# ip_phone_a_sdram.net
KiCad netlist of a schematic drawn in Altium Designer
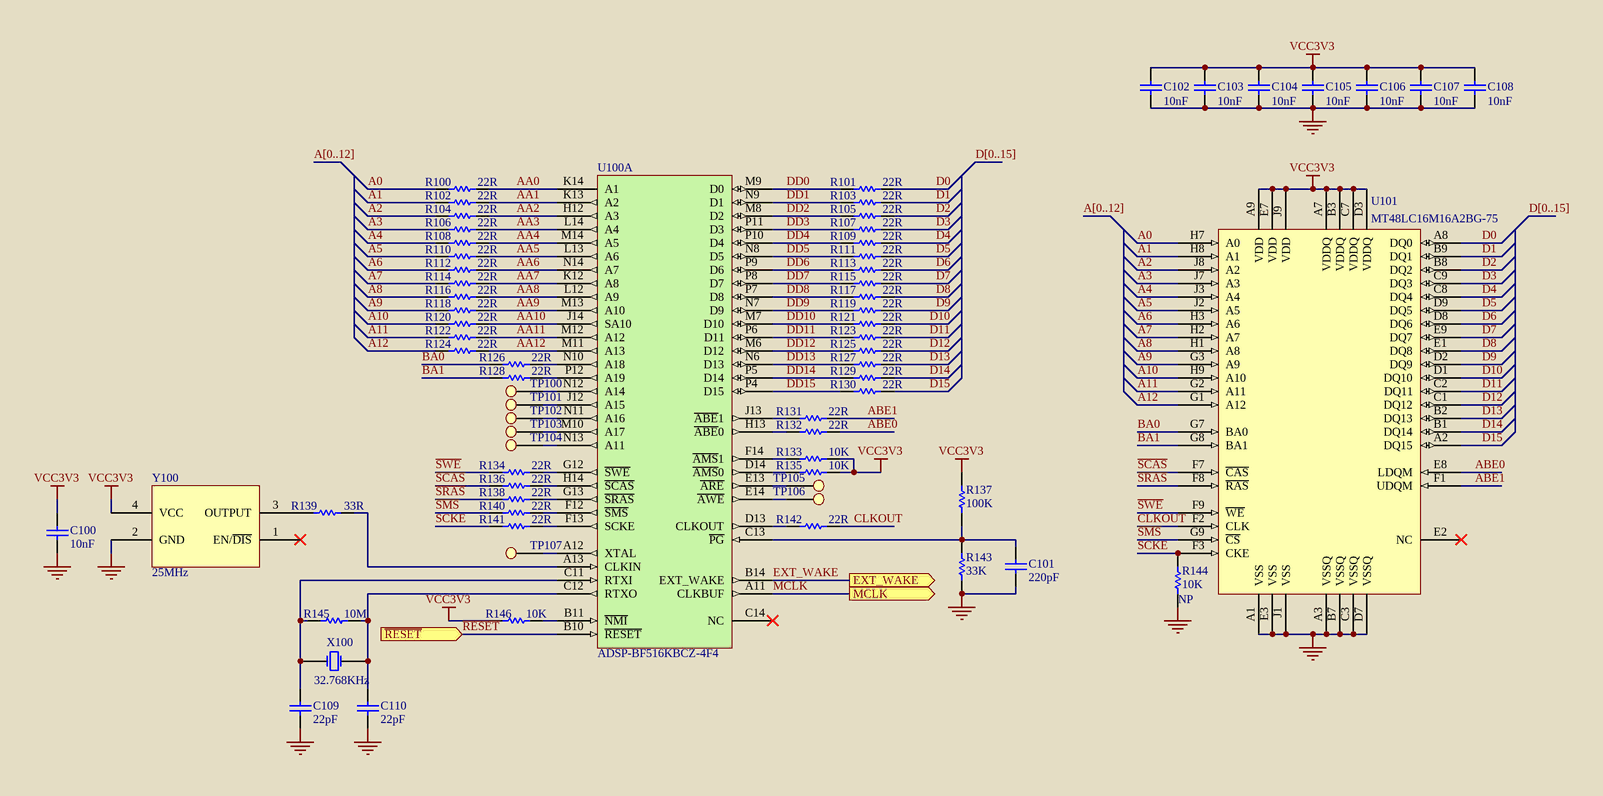
[diagram p0: ip_phone_a_sdram.SchDoc]

(export (version "E")
  (design (tool "Eeschema 10.0.6"))
  (components
    (comp (ref "C100")
      (value "10nF")
      (footprint "ip_phone:CC1005-0402")
      (description "Ceramic Capacitor 10nF 50V X7R 0402")
      (fields (field (name "EVENDORPART#") "810-C1005X7R1C103K") (field (name "MANUFACTURER") "TDK"))
      (libsource (lib "ip_phone") (part "Capacitor"))
    )
    (comp (ref "C101")
      (value "220pF")
      (footprint "ip_phone:CC1005-0402")
      (description "Capacitor")
      (fields (field (name "EVENDORPART#") "311-1035-1-ND") (field (name "MANUFACTURER") "Yageo"))
      (libsource (lib "ip_phone") (part "Capacitor"))
    )
    (comp (ref "C102")
      (value "10nF")
      (footprint "ip_phone:CC1005-0402")
      (description "Ceramic Capacitor 0.01uF 50V X7R 0402")
      (fields (field (name "EVENDORPART#") "810-C1005X7R1C103K") (field (name "MANUFACTURER") "TDK"))
      (libsource (lib "ip_phone") (part "Capacitor"))
    )
    (comp (ref "C103")
      (value "10nF")
      (footprint "ip_phone:CC1005-0402")
      (description "Ceramic Capacitor 0.01uF 50V X7R 0402")
      (fields (field (name "EVENDORPART#") "810-C1005X7R1C103K") (field (name "MANUFACTURER") "TDK"))
      (libsource (lib "ip_phone") (part "Capacitor"))
    )
    (comp (ref "C104")
      (value "10nF")
      (footprint "ip_phone:CC1005-0402")
      (description "Ceramic Capacitor 0.01uF 50V X7R 0402")
      (fields (field (name "EVENDORPART#") "810-C1005X7R1C103K") (field (name "MANUFACTURER") "TDK"))
      (libsource (lib "ip_phone") (part "Capacitor"))
    )
    (comp (ref "C105")
      (value "10nF")
      (footprint "ip_phone:CC1005-0402")
      (description "Ceramic Capacitor 0.01uF 50V X7R 0402")
      (fields (field (name "EVENDORPART#") "810-C1005X7R1C103K") (field (name "MANUFACTURER") "TDK"))
      (libsource (lib "ip_phone") (part "Capacitor"))
    )
    (comp (ref "C106")
      (value "10nF")
      (footprint "ip_phone:CC1005-0402")
      (description "Ceramic Capacitor 0.01uF 50V X7R 0402")
      (fields (field (name "EVENDORPART#") "810-C1005X7R1C103K") (field (name "MANUFACTURER") "TDK"))
      (libsource (lib "ip_phone") (part "Capacitor"))
    )
    (comp (ref "C107")
      (value "10nF")
      (footprint "ip_phone:CC1005-0402")
      (description "Ceramic Capacitor 0.01uF 50V X7R 0402")
      (fields (field (name "EVENDORPART#") "810-C1005X7R1C103K") (field (name "MANUFACTURER") "TDK"))
      (libsource (lib "ip_phone") (part "Capacitor"))
    )
    (comp (ref "C108")
      (value "10nF")
      (footprint "ip_phone:CC1005-0402")
      (description "Ceramic Capacitor 0.01uF 50V X7R 0402")
      (fields (field (name "EVENDORPART#") "810-C1005X7R1C103K") (field (name "MANUFACTURER") "TDK"))
      (libsource (lib "ip_phone") (part "Capacitor"))
    )
    (comp (ref "C109")
      (value "22pF")
      (footprint "ip_phone:CC1005-0402")
      (description "Ceramic Capacitor 22pF 50V 5% C0G 0402")
      (fields
        (field (name "EVENDORPART#") "490-1283-1-ND")
        (field (name "MANUFACTURER") "Murata Electronics North America")
      )
      (libsource (lib "ip_phone") (part "Capacitor"))
    )
    (comp (ref "C110")
      (value "22pF")
      (footprint "ip_phone:CC1005-0402")
      (description "Ceramic Capacitor 22pF 50V 5% C0G 0402")
      (fields
        (field (name "EVENDORPART#") "490-1283-1-ND")
        (field (name "MANUFACTURER") "Murata Electronics North America")
      )
      (libsource (lib "ip_phone") (part "Capacitor"))
    )
    (comp (ref "R100")
      (value "22R")
      (footprint "ip_phone:CR1005-0402")
      (description "Thick Film Resistors SMD 0402 22R 5%  1/16 W")
      (fields (field (name "EVENDORPART#") "71-CRCW0402J-22-E3") (field (name "MANUFACTURER") "Vishay/Dale"))
      (libsource (lib "ip_phone") (part "Resistor"))
    )
    (comp (ref "R101")
      (value "22R")
      (footprint "ip_phone:CR1005-0402")
      (description "Thick Film Resistors SMD 0402 22R 5%  1/16 W")
      (fields (field (name "EVENDORPART#") "71-CRCW0402J-22-E3") (field (name "MANUFACTURER") "Vishay/Dale"))
      (libsource (lib "ip_phone") (part "Resistor"))
    )
    (comp (ref "R102")
      (value "22R")
      (footprint "ip_phone:CR1005-0402")
      (description "Thick Film Resistors SMD 0402 22R 5%  1/16 W")
      (fields (field (name "EVENDORPART#") "71-CRCW0402J-22-E3") (field (name "MANUFACTURER") "Vishay/Dale"))
      (libsource (lib "ip_phone") (part "Resistor"))
    )
    (comp (ref "R103")
      (value "22R")
      (footprint "ip_phone:CR1005-0402")
      (description "Thick Film Resistors SMD 0402 22R 5%  1/16 W")
      (fields (field (name "EVENDORPART#") "71-CRCW0402J-22-E3") (field (name "MANUFACTURER") "Vishay/Dale"))
      (libsource (lib "ip_phone") (part "Resistor"))
    )
    (comp (ref "R104")
      (value "22R")
      (footprint "ip_phone:CR1005-0402")
      (description "Thick Film Resistors SMD 0402 22R 5%  1/16 W")
      (fields (field (name "EVENDORPART#") "71-CRCW0402J-22-E3") (field (name "MANUFACTURER") "Vishay/Dale"))
      (libsource (lib "ip_phone") (part "Resistor"))
    )
    (comp (ref "R105")
      (value "22R")
      (footprint "ip_phone:CR1005-0402")
      (description "Thick Film Resistors SMD 0402 22R 5%  1/16 W")
      (fields (field (name "EVENDORPART#") "71-CRCW0402J-22-E3") (field (name "MANUFACTURER") "Vishay/Dale"))
      (libsource (lib "ip_phone") (part "Resistor"))
    )
    (comp (ref "R106")
      (value "22R")
      (footprint "ip_phone:CR1005-0402")
      (description "Thick Film Resistors SMD 0402 22R 5%  1/16 W")
      (fields (field (name "EVENDORPART#") "71-CRCW0402J-22-E3") (field (name "MANUFACTURER") "Vishay/Dale"))
      (libsource (lib "ip_phone") (part "Resistor"))
    )
    (comp (ref "R107")
      (value "22R")
      (footprint "ip_phone:CR1005-0402")
      (description "Thick Film Resistors SMD 0402 22R 5%  1/16 W")
      (fields (field (name "EVENDORPART#") "71-CRCW0402J-22-E3") (field (name "MANUFACTURER") "Vishay/Dale"))
      (libsource (lib "ip_phone") (part "Resistor"))
    )
    (comp (ref "R108")
      (value "22R")
      (footprint "ip_phone:CR1005-0402")
      (description "Thick Film Resistors SMD 0402 22R 5%  1/16 W")
      (fields (field (name "EVENDORPART#") "71-CRCW0402J-22-E3") (field (name "MANUFACTURER") "Vishay/Dale"))
      (libsource (lib "ip_phone") (part "Resistor"))
    )
    (comp (ref "R109")
      (value "22R")
      (footprint "ip_phone:CR1005-0402")
      (description "Thick Film Resistors SMD 0402 22R 5%  1/16 W")
      (fields (field (name "EVENDORPART#") "71-CRCW0402J-22-E3") (field (name "MANUFACTURER") "Vishay/Dale"))
      (libsource (lib "ip_phone") (part "Resistor"))
    )
    (comp (ref "R110")
      (value "22R")
      (footprint "ip_phone:CR1005-0402")
      (description "Thick Film Resistors SMD 0402 22R 5%  1/16 W")
      (fields (field (name "EVENDORPART#") "71-CRCW0402J-22-E3") (field (name "MANUFACTURER") "Vishay/Dale"))
      (libsource (lib "ip_phone") (part "Resistor"))
    )
    (comp (ref "R111")
      (value "22R")
      (footprint "ip_phone:CR1005-0402")
      (description "Thick Film Resistors SMD 0402 22R 5%  1/16 W")
      (fields (field (name "EVENDORPART#") "71-CRCW0402J-22-E3") (field (name "MANUFACTURER") "Vishay/Dale"))
      (libsource (lib "ip_phone") (part "Resistor"))
    )
    (comp (ref "R112")
      (value "22R")
      (footprint "ip_phone:CR1005-0402")
      (description "Thick Film Resistors SMD 0402 22R 5%  1/16 W")
      (fields (field (name "EVENDORPART#") "71-CRCW0402J-22-E3") (field (name "MANUFACTURER") "Vishay/Dale"))
      (libsource (lib "ip_phone") (part "Resistor"))
    )
    (comp (ref "R113")
      (value "22R")
      (footprint "ip_phone:CR1005-0402")
      (description "Thick Film Resistors SMD 0402 22R 5%  1/16 W")
      (fields (field (name "EVENDORPART#") "71-CRCW0402J-22-E3") (field (name "MANUFACTURER") "Vishay/Dale"))
      (libsource (lib "ip_phone") (part "Resistor"))
    )
    (comp (ref "R114")
      (value "22R")
      (footprint "ip_phone:CR1005-0402")
      (description "Thick Film Resistors SMD 0402 22R 5%  1/16 W")
      (fields (field (name "EVENDORPART#") "71-CRCW0402J-22-E3") (field (name "MANUFACTURER") "Vishay/Dale"))
      (libsource (lib "ip_phone") (part "Resistor"))
    )
    (comp (ref "R115")
      (value "22R")
      (footprint "ip_phone:CR1005-0402")
      (description "Thick Film Resistors SMD 0402 22R 5%  1/16 W")
      (fields (field (name "EVENDORPART#") "71-CRCW0402J-22-E3") (field (name "MANUFACTURER") "Vishay/Dale"))
      (libsource (lib "ip_phone") (part "Resistor"))
    )
    (comp (ref "R116")
      (value "22R")
      (footprint "ip_phone:CR1005-0402")
      (description "Thick Film Resistors SMD 0402 22R 5%  1/16 W")
      (fields (field (name "EVENDORPART#") "71-CRCW0402J-22-E3") (field (name "MANUFACTURER") "Vishay/Dale"))
      (libsource (lib "ip_phone") (part "Resistor"))
    )
    (comp (ref "R117")
      (value "22R")
      (footprint "ip_phone:CR1005-0402")
      (description "Thick Film Resistors SMD 0402 22R 5%  1/16 W")
      (fields (field (name "EVENDORPART#") "71-CRCW0402J-22-E3") (field (name "MANUFACTURER") "Vishay/Dale"))
      (libsource (lib "ip_phone") (part "Resistor"))
    )
    (comp (ref "R118")
      (value "22R")
      (footprint "ip_phone:CR1005-0402")
      (description "Thick Film Resistors SMD 0402 22R 5%  1/16 W")
      (fields (field (name "EVENDORPART#") "71-CRCW0402J-22-E3") (field (name "MANUFACTURER") "Vishay/Dale"))
      (libsource (lib "ip_phone") (part "Resistor"))
    )
    (comp (ref "R119")
      (value "22R")
      (footprint "ip_phone:CR1005-0402")
      (description "Thick Film Resistors SMD 0402 22R 5%  1/16 W")
      (fields (field (name "EVENDORPART#") "71-CRCW0402J-22-E3") (field (name "MANUFACTURER") "Vishay/Dale"))
      (libsource (lib "ip_phone") (part "Resistor"))
    )
    (comp (ref "R120")
      (value "22R")
      (footprint "ip_phone:CR1005-0402")
      (description "Thick Film Resistors SMD 0402 22R 5%  1/16 W")
      (fields (field (name "EVENDORPART#") "71-CRCW0402J-22-E3") (field (name "MANUFACTURER") "Vishay/Dale"))
      (libsource (lib "ip_phone") (part "Resistor"))
    )
    (comp (ref "R121")
      (value "22R")
      (footprint "ip_phone:CR1005-0402")
      (description "Thick Film Resistors SMD 0402 22R 5%  1/16 W")
      (fields (field (name "EVENDORPART#") "71-CRCW0402J-22-E3") (field (name "MANUFACTURER") "Vishay/Dale"))
      (libsource (lib "ip_phone") (part "Resistor"))
    )
    (comp (ref "R122")
      (value "22R")
      (footprint "ip_phone:CR1005-0402")
      (description "Thick Film Resistors SMD 0402 22R 5%  1/16 W")
      (fields (field (name "EVENDORPART#") "71-CRCW0402J-22-E3") (field (name "MANUFACTURER") "Vishay/Dale"))
      (libsource (lib "ip_phone") (part "Resistor"))
    )
    (comp (ref "R123")
      (value "22R")
      (footprint "ip_phone:CR1005-0402")
      (description "Thick Film Resistors SMD 0402 22R 5%  1/16 W")
      (fields (field (name "EVENDORPART#") "71-CRCW0402J-22-E3") (field (name "MANUFACTURER") "Vishay/Dale"))
      (libsource (lib "ip_phone") (part "Resistor"))
    )
    (comp (ref "R124")
      (value "22R")
      (footprint "ip_phone:CR1005-0402")
      (description "Thick Film Resistors SMD 0402 22R 5%  1/16 W")
      (fields (field (name "EVENDORPART#") "71-CRCW0402J-22-E3") (field (name "MANUFACTURER") "Vishay/Dale"))
      (libsource (lib "ip_phone") (part "Resistor"))
    )
    (comp (ref "R125")
      (value "22R")
      (footprint "ip_phone:CR1005-0402")
      (description "Thick Film Resistors SMD 0402 22R 5%  1/16 W")
      (fields (field (name "EVENDORPART#") "71-CRCW0402J-22-E3") (field (name "MANUFACTURER") "Vishay/Dale"))
      (libsource (lib "ip_phone") (part "Resistor"))
    )
    (comp (ref "R126")
      (value "22R")
      (footprint "ip_phone:CR1005-0402")
      (description "Thick Film Resistors SMD 0402 22R 5%  1/16 W")
      (fields (field (name "EVENDORPART#") "71-CRCW0402J-22-E3") (field (name "MANUFACTURER") "Vishay/Dale"))
      (libsource (lib "ip_phone") (part "Resistor"))
    )
    (comp (ref "R127")
      (value "22R")
      (footprint "ip_phone:CR1005-0402")
      (description "Thick Film Resistors SMD 0402 22R 5%  1/16 W")
      (fields (field (name "EVENDORPART#") "71-CRCW0402J-22-E3") (field (name "MANUFACTURER") "Vishay/Dale"))
      (libsource (lib "ip_phone") (part "Resistor"))
    )
    (comp (ref "R128")
      (value "22R")
      (footprint "ip_phone:CR1005-0402")
      (description "Thick Film Resistors SMD 0402 22R 5%  1/16 W")
      (fields (field (name "EVENDORPART#") "71-CRCW0402J-22-E3") (field (name "MANUFACTURER") "Vishay/Dale"))
      (libsource (lib "ip_phone") (part "Resistor"))
    )
    (comp (ref "R129")
      (value "22R")
      (footprint "ip_phone:CR1005-0402")
      (description "Thick Film Resistors SMD 0402 22R 5%  1/16 W")
      (fields (field (name "EVENDORPART#") "71-CRCW0402J-22-E3") (field (name "MANUFACTURER") "Vishay/Dale"))
      (libsource (lib "ip_phone") (part "Resistor"))
    )
    (comp (ref "R130")
      (value "22R")
      (footprint "ip_phone:CR1005-0402")
      (description "Thick Film Resistors SMD 0402 22R 5%  1/16 W")
      (fields (field (name "EVENDORPART#") "71-CRCW0402J-22-E3") (field (name "MANUFACTURER") "Vishay/Dale"))
      (libsource (lib "ip_phone") (part "Resistor"))
    )
    (comp (ref "R131")
      (value "22R")
      (footprint "ip_phone:CR1005-0402")
      (description "Thick Film Resistors SMD 0402 22R 5%  1/16 W")
      (fields (field (name "EVENDORPART#") "71-CRCW0402J-22-E3") (field (name "MANUFACTURER") "Vishay/Dale"))
      (libsource (lib "ip_phone") (part "Resistor"))
    )
    (comp (ref "R132")
      (value "22R")
      (footprint "ip_phone:CR1005-0402")
      (description "Thick Film Resistors SMD 0402 22R 5%  1/16 W")
      (fields (field (name "EVENDORPART#") "71-CRCW0402J-22-E3") (field (name "MANUFACTURER") "Vishay/Dale"))
      (libsource (lib "ip_phone") (part "Resistor"))
    )
    (comp (ref "R133")
      (value "10K")
      (footprint "ip_phone:CR1005-0402")
      (description "Thick Film Resistors SMD 0402 10k 5%  1/16 W")
      (fields (field (name "EVENDORPART#") "311-10KJRCT-ND") (field (name "MANUFACTURER") "Yageo"))
      (libsource (lib "ip_phone") (part "Resistor"))
    )
    (comp (ref "R134")
      (value "22R")
      (footprint "ip_phone:CR1005-0402")
      (description "Thick Film Resistors SMD 0402 22R 5%  1/16 W")
      (fields (field (name "EVENDORPART#") "71-CRCW0402J-22-E3") (field (name "MANUFACTURER") "Vishay/Dale"))
      (libsource (lib "ip_phone") (part "Resistor"))
    )
    (comp (ref "R135")
      (value "10K")
      (footprint "ip_phone:CR1005-0402")
      (description "Thick Film Resistors SMD 0402 10k 5%  1/16 W")
      (fields (field (name "EVENDORPART#") "311-10KJRCT-ND") (field (name "MANUFACTURER") "Yageo"))
      (libsource (lib "ip_phone") (part "Resistor"))
    )
    (comp (ref "R136")
      (value "22R")
      (footprint "ip_phone:CR1005-0402")
      (description "Thick Film Resistors SMD 0402 22R 5%  1/16 W")
      (fields (field (name "EVENDORPART#") "71-CRCW0402J-22-E3") (field (name "MANUFACTURER") "Vishay/Dale"))
      (libsource (lib "ip_phone") (part "Resistor"))
    )
    (comp (ref "R137")
      (value "100K")
      (footprint "ip_phone:CR1005-0402")
      (description "Thick Film Resistors SMD 0402 100K 5%  1/16 W")
      (fields (field (name "EVENDORPART#") "311-100KJRCT-ND") (field (name "MANUFACTURER") "Yageo"))
      (libsource (lib "ip_phone") (part "Resistor"))
    )
    (comp (ref "R138")
      (value "22R")
      (footprint "ip_phone:CR1005-0402")
      (description "Thick Film Resistors SMD 0402 22R 5%  1/16 W")
      (fields (field (name "EVENDORPART#") "71-CRCW0402J-22-E3") (field (name "MANUFACTURER") "Vishay/Dale"))
      (libsource (lib "ip_phone") (part "Resistor"))
    )
    (comp (ref "R139")
      (value "33R")
      (footprint "ip_phone:CR1005-0402")
      (description "Thick Film Resistors SMD 0402 33R 5%  1/16 W")
      (fields (field (name "EVENDORPART#") "311-33JRCT-ND") (field (name "MANUFACTURER") "Yageo"))
      (libsource (lib "ip_phone") (part "Resistor"))
    )
    (comp (ref "R140")
      (value "22R")
      (footprint "ip_phone:CR1005-0402")
      (description "Thick Film Resistors SMD 0402 22R 5%  1/16 W")
      (fields (field (name "EVENDORPART#") "71-CRCW0402J-22-E3") (field (name "MANUFACTURER") "Vishay/Dale"))
      (libsource (lib "ip_phone") (part "Resistor"))
    )
    (comp (ref "R141")
      (value "22R")
      (footprint "ip_phone:CR1005-0402")
      (description "Thick Film Resistors SMD 0402 22R 5%  1/16 W")
      (fields (field (name "EVENDORPART#") "71-CRCW0402J-22-E3") (field (name "MANUFACTURER") "Vishay/Dale"))
      (libsource (lib "ip_phone") (part "Resistor"))
    )
    (comp (ref "R142")
      (value "22R")
      (footprint "ip_phone:CR1005-0402")
      (description "Thick Film Resistors SMD 0402 22R 5%  1/16 W")
      (fields (field (name "EVENDORPART#") "71-CRCW0402J-22-E3") (field (name "MANUFACTURER") "Vishay/Dale"))
      (libsource (lib "ip_phone") (part "Resistor"))
    )
    (comp (ref "R143")
      (value "33K")
      (footprint "ip_phone:CR1005-0402")
      (description "Thick Film Resistors SMD 0402 33K 5%  1/16 W")
      (fields (field (name "EVENDORPART#") "311-33KJRCT-ND") (field (name "MANUFACTURER") "Yageo"))
      (libsource (lib "ip_phone") (part "Resistor"))
    )
    (comp (ref "R144")
      (value "10K")
      (footprint "ip_phone:CR1005-0402_NP")
      (description "Thick Film Resistors SMD 0402 10K 5%  1/16 W")
      (fields
        (field (name "EVENDORPART#") "311-10KJRCT-ND")
        (field (name "MANUFACTURER") "Yageo")
        (field (name "NP") "NP")
      )
      (libsource (lib "ip_phone") (part "Resistor"))
    )
    (comp (ref "R145")
      (value "10M")
      (footprint "ip_phone:CR1005-0402")
      (description "Thick Film Resistors SMD 0402 10M 5%  1/16 W")
      (fields
        (field (name "EVENDORPART#") "RMCF0402JT10M0CT-ND")
        (field (name "MANUFACTURER") "Stackpole Electronics Inc")
      )
      (libsource (lib "ip_phone") (part "Resistor"))
    )
    (comp (ref "R146")
      (value "10K")
      (footprint "ip_phone:CR1005-0402")
      (description "Thick Film Resistors SMD 0402 10K 5%  1/16 W")
      (fields (field (name "EVENDORPART#") "311-10KJRCT-ND") (field (name "MANUFACTURER") "Yageo"))
      (libsource (lib "ip_phone") (part "Resistor"))
    )
    (comp (ref "TP100")
      (value "Test Point")
      (footprint "ip_phone:Test Point")
      (fields (field (name "EVENDORPART#") "NÃO SE APLICA"))
      (libsource (lib "ip_phone") (part "Test Point"))
    )
    (comp (ref "TP101")
      (value "Test Point")
      (footprint "ip_phone:Test Point")
      (fields (field (name "EVENDORPART#") "NÃO SE APLICA"))
      (libsource (lib "ip_phone") (part "Test Point"))
    )
    (comp (ref "TP102")
      (value "Test Point")
      (footprint "ip_phone:Test Point")
      (fields (field (name "EVENDORPART#") "NÃO SE APLICA"))
      (libsource (lib "ip_phone") (part "Test Point"))
    )
    (comp (ref "TP103")
      (value "Test Point")
      (footprint "ip_phone:Test Point")
      (fields (field (name "EVENDORPART#") "NÃO SE APLICA"))
      (libsource (lib "ip_phone") (part "Test Point"))
    )
    (comp (ref "TP104")
      (value "Test Point")
      (footprint "ip_phone:Test Point")
      (fields (field (name "EVENDORPART#") "NÃO SE APLICA"))
      (libsource (lib "ip_phone") (part "Test Point"))
    )
    (comp (ref "TP105")
      (value "Test Point")
      (footprint "ip_phone:Test Point")
      (fields (field (name "EVENDORPART#") "NÃO SE APLICA"))
      (libsource (lib "ip_phone") (part "Test Point"))
    )
    (comp (ref "TP106")
      (value "Test Point")
      (footprint "ip_phone:Test Point")
      (fields (field (name "EVENDORPART#") "NÃO SE APLICA"))
      (libsource (lib "ip_phone") (part "Test Point"))
    )
    (comp (ref "TP107")
      (value "Test Point")
      (footprint "ip_phone:Test Point")
      (fields (field (name "EVENDORPART#") "NÃO SE APLICA"))
      (libsource (lib "ip_phone") (part "Test Point"))
    )
    (comp (ref "U100")
      (value "ADSP-BF516KBCZ-4F4")
      (footprint "ip_phone:BGA168")
      (description "Low Power Blackfin with Advanced Embedded Connectivity")
      (fields (field (name "MANUFACTURER") "Analog Device"))
      (libsource (lib "ip_phone") (part "ADSP-BF516KBCZ-4F4"))
    )
    (comp (ref "U101")
      (value "MT48LC16M16A2BG-75")
      (footprint "ip_phone:VFBGA54")
      (description "SDRAM 256M-Bit 16Mx16 3.3V 54-Pin VFBGA Tray")
      (fields (field (name "EVENDORPART#") "MT48LC16M16A2BG-75 IT:D") (field (name "MANUFACTURER") "Micron"))
      (libsource (lib "ip_phone") (part "MT48LC16M16A2BG-75"))
    )
    (comp (ref "X100")
      (value "32.768KHz")
      (footprint "ip_phone:XTAL_32.768kHz")
      (description "Crystal 32.768KHz")
      (fields
        (field (name "EVENDORPART#") "732-MC30632.7680KA0R")
        (field (name "PART#") "MC-306 32.7680K-A0:ROHS")
      )
      (libsource (lib "ip_phone") (part "XTAL_32.768KHz"))
    )
    (comp (ref "Y100")
      (value "25MHz")
      (footprint "ip_phone:OSC_25MHz")
      (description "Crystal Clock Oscillator 25MHz  50ppm 3.3V")
      (fields (field (name "EVENDORPART#") "300-8254-1-ND") (field (name "PART#") "ASFL1-25.000MHZ-EC-T"))
      (libsource (lib "ip_phone") (part "Oscillator_25MHz"))
    )
  )
  (nets
    (net (code "1") (name "/A0") (class "Default")
      (node (ref "R100") (pin "1") (pinfunction "1_1") (pintype "passive"))
      (node (ref "U101") (pin "H7") (pinfunction "A0_H7") (pintype "input"))
    )
    (net (code "2") (name "/A1") (class "Default")
      (node (ref "R102") (pin "1") (pinfunction "1_1") (pintype "passive"))
      (node (ref "U101") (pin "H8") (pinfunction "A1_H8") (pintype "input"))
    )
    (net (code "3") (name "/A2") (class "Default")
      (node (ref "R104") (pin "1") (pinfunction "1_1") (pintype "passive"))
      (node (ref "U101") (pin "J8") (pinfunction "A2_J8") (pintype "input"))
    )
    (net (code "4") (name "/A3") (class "Default")
      (node (ref "R106") (pin "1") (pinfunction "1_1") (pintype "passive"))
      (node (ref "U101") (pin "J7") (pinfunction "A3_J7") (pintype "input"))
    )
    (net (code "5") (name "/A4") (class "Default")
      (node (ref "R108") (pin "1") (pinfunction "1_1") (pintype "passive"))
      (node (ref "U101") (pin "J3") (pinfunction "A4_J3") (pintype "input"))
    )
    (net (code "6") (name "/A5") (class "Default")
      (node (ref "R110") (pin "1") (pinfunction "1_1") (pintype "passive"))
      (node (ref "U101") (pin "J2") (pinfunction "A5_J2") (pintype "input"))
    )
    (net (code "7") (name "/A6") (class "Default")
      (node (ref "R112") (pin "1") (pinfunction "1_1") (pintype "passive"))
      (node (ref "U101") (pin "H3") (pinfunction "A6_H3") (pintype "input"))
    )
    (net (code "8") (name "/A7") (class "Default")
      (node (ref "R114") (pin "1") (pinfunction "1_1") (pintype "passive"))
      (node (ref "U101") (pin "H2") (pinfunction "A7_H2") (pintype "input"))
    )
    (net (code "9") (name "/A8") (class "Default")
      (node (ref "R116") (pin "1") (pinfunction "1_1") (pintype "passive"))
      (node (ref "U101") (pin "H1") (pinfunction "A8_H1") (pintype "input"))
    )
    (net (code "10") (name "/A9") (class "Default")
      (node (ref "R118") (pin "1") (pinfunction "1_1") (pintype "passive"))
      (node (ref "U101") (pin "G3") (pinfunction "A9_G3") (pintype "input"))
    )
    (net (code "11") (name "/A10") (class "Default")
      (node (ref "R120") (pin "1") (pinfunction "1_1") (pintype "passive"))
      (node (ref "U101") (pin "H9") (pinfunction "A10_H9") (pintype "input"))
    )
    (net (code "12") (name "/A11") (class "Default")
      (node (ref "R122") (pin "1") (pinfunction "1_1") (pintype "passive"))
      (node (ref "U101") (pin "G2") (pinfunction "A11_G2") (pintype "input"))
    )
    (net (code "13") (name "/A12") (class "Default")
      (node (ref "R124") (pin "1") (pinfunction "1_1") (pintype "passive"))
      (node (ref "U101") (pin "G1") (pinfunction "A12_G1") (pintype "input"))
    )
    (net (code "14") (name "/AA0") (class "Default")
      (node (ref "R100") (pin "2") (pinfunction "2_2") (pintype "passive"))
      (node (ref "U100") (pin "K14") (pinfunction "A1_K14") (pintype "passive"))
    )
    (net (code "15") (name "/AA1") (class "Default")
      (node (ref "R102") (pin "2") (pinfunction "2_2") (pintype "passive"))
      (node (ref "U100") (pin "K13") (pinfunction "A2_K13") (pintype "output"))
    )
    (net (code "16") (name "/AA2") (class "Default")
      (node (ref "R104") (pin "2") (pinfunction "2_2") (pintype "passive"))
      (node (ref "U100") (pin "H12") (pinfunction "A3_H12") (pintype "output"))
    )
    (net (code "17") (name "/AA3") (class "Default")
      (node (ref "R106") (pin "2") (pinfunction "2_2") (pintype "passive"))
      (node (ref "U100") (pin "L14") (pinfunction "A4_L14") (pintype "output"))
    )
    (net (code "18") (name "/AA4") (class "Default")
      (node (ref "R108") (pin "2") (pinfunction "2_2") (pintype "passive"))
      (node (ref "U100") (pin "M14") (pinfunction "A5_M14") (pintype "output"))
    )
    (net (code "19") (name "/AA5") (class "Default")
      (node (ref "R110") (pin "2") (pinfunction "2_2") (pintype "passive"))
      (node (ref "U100") (pin "L13") (pinfunction "A6_L13") (pintype "output"))
    )
    (net (code "20") (name "/AA6") (class "Default")
      (node (ref "R112") (pin "2") (pinfunction "2_2") (pintype "passive"))
      (node (ref "U100") (pin "N14") (pinfunction "A7_N14") (pintype "output"))
    )
    (net (code "21") (name "/AA7") (class "Default")
      (node (ref "R114") (pin "2") (pinfunction "2_2") (pintype "passive"))
      (node (ref "U100") (pin "K12") (pinfunction "A8_K12") (pintype "output"))
    )
    (net (code "22") (name "/AA8") (class "Default")
      (node (ref "R116") (pin "2") (pinfunction "2_2") (pintype "passive"))
      (node (ref "U100") (pin "L12") (pinfunction "A9_L12") (pintype "output"))
    )
    (net (code "23") (name "/AA9") (class "Default")
      (node (ref "R118") (pin "2") (pinfunction "2_2") (pintype "passive"))
      (node (ref "U100") (pin "M13") (pinfunction "A10_M13") (pintype "output"))
    )
    (net (code "24") (name "/AA10") (class "Default")
      (node (ref "R120") (pin "2") (pinfunction "2_2") (pintype "passive"))
      (node (ref "U100") (pin "J14") (pinfunction "SA10_J14") (pintype "output"))
    )
    (net (code "25") (name "/AA11") (class "Default")
      (node (ref "R122") (pin "2") (pinfunction "2_2") (pintype "passive"))
      (node (ref "U100") (pin "M12") (pinfunction "A12_M12") (pintype "output"))
    )
    (net (code "26") (name "/AA12") (class "Default")
      (node (ref "R124") (pin "2") (pinfunction "2_2") (pintype "passive"))
      (node (ref "U100") (pin "M11") (pinfunction "A13_M11") (pintype "output"))
    )
    (net (code "27") (name "/ABE0") (class "Default")
      (node (ref "R132") (pin "2") (pinfunction "2_2") (pintype "passive"))
      (node (ref "U101") (pin "E8") (pinfunction "LDQM_E8") (pintype "input"))
    )
    (net (code "28") (name "/ABE1") (class "Default")
      (node (ref "R131") (pin "2") (pinfunction "2_2") (pintype "passive"))
      (node (ref "U101") (pin "F1") (pinfunction "UDQM_F1") (pintype "input"))
    )
    (net (code "30") (name "/BA0") (class "Default")
      (node (ref "R126") (pin "1") (pinfunction "1_1") (pintype "passive"))
      (node (ref "U101") (pin "G7") (pinfunction "BA0_G7") (pintype "input"))
    )
    (net (code "31") (name "/BA1") (class "Default")
      (node (ref "R128") (pin "1") (pinfunction "1_1") (pintype "passive"))
      (node (ref "U101") (pin "G8") (pinfunction "BA1_G8") (pintype "input"))
    )
    (net (code "32") (name "/CLKOUT") (class "Default")
      (node (ref "R142") (pin "2") (pinfunction "2_2") (pintype "passive"))
      (node (ref "U101") (pin "F2") (pinfunction "CLK_F2") (pintype "input"))
    )
    (net (code "33") (name "/D0") (class "Default")
      (node (ref "R101") (pin "2") (pinfunction "2_2") (pintype "passive"))
      (node (ref "U101") (pin "A8") (pinfunction "DQ0_A8") (pintype "bidirectional"))
    )
    (net (code "34") (name "/D1") (class "Default")
      (node (ref "R103") (pin "2") (pinfunction "2_2") (pintype "passive"))
      (node (ref "U101") (pin "B9") (pinfunction "DQ1_B9") (pintype "bidirectional"))
    )
    (net (code "35") (name "/D2") (class "Default")
      (node (ref "R105") (pin "2") (pinfunction "2_2") (pintype "passive"))
      (node (ref "U101") (pin "B8") (pinfunction "DQ2_B8") (pintype "bidirectional"))
    )
    (net (code "36") (name "/D3") (class "Default")
      (node (ref "R107") (pin "2") (pinfunction "2_2") (pintype "passive"))
      (node (ref "U101") (pin "C9") (pinfunction "DQ3_C9") (pintype "bidirectional"))
    )
    (net (code "37") (name "/D4") (class "Default")
      (node (ref "R109") (pin "2") (pinfunction "2_2") (pintype "passive"))
      (node (ref "U101") (pin "C8") (pinfunction "DQ4_C8") (pintype "bidirectional"))
    )
    (net (code "38") (name "/D5") (class "Default")
      (node (ref "R111") (pin "2") (pinfunction "2_2") (pintype "passive"))
      (node (ref "U101") (pin "D9") (pinfunction "DQ5_D9") (pintype "bidirectional"))
    )
    (net (code "39") (name "/D6") (class "Default")
      (node (ref "R113") (pin "2") (pinfunction "2_2") (pintype "passive"))
      (node (ref "U101") (pin "D8") (pinfunction "DQ6_D8") (pintype "bidirectional"))
    )
    (net (code "40") (name "/D7") (class "Default")
      (node (ref "R115") (pin "2") (pinfunction "2_2") (pintype "passive"))
      (node (ref "U101") (pin "E9") (pinfunction "DQ7_E9") (pintype "bidirectional"))
    )
    (net (code "41") (name "/D8") (class "Default")
      (node (ref "R117") (pin "2") (pinfunction "2_2") (pintype "passive"))
      (node (ref "U101") (pin "E1") (pinfunction "DQ8_E1") (pintype "bidirectional"))
    )
    (net (code "42") (name "/D9") (class "Default")
      (node (ref "R119") (pin "2") (pinfunction "2_2") (pintype "passive"))
      (node (ref "U101") (pin "D2") (pinfunction "DQ9_D2") (pintype "bidirectional"))
    )
    (net (code "43") (name "/D10") (class "Default")
      (node (ref "R121") (pin "2") (pinfunction "2_2") (pintype "passive"))
      (node (ref "U101") (pin "D1") (pinfunction "DQ10_D1") (pintype "bidirectional"))
    )
    (net (code "44") (name "/D11") (class "Default")
      (node (ref "R123") (pin "2") (pinfunction "2_2") (pintype "passive"))
      (node (ref "U101") (pin "C2") (pinfunction "DQ11_C2") (pintype "bidirectional"))
    )
    (net (code "45") (name "/D12") (class "Default")
      (node (ref "R125") (pin "2") (pinfunction "2_2") (pintype "passive"))
      (node (ref "U101") (pin "C1") (pinfunction "DQ12_C1") (pintype "bidirectional"))
    )
    (net (code "46") (name "/D13") (class "Default")
      (node (ref "R127") (pin "2") (pinfunction "2_2") (pintype "passive"))
      (node (ref "U101") (pin "B2") (pinfunction "DQ13_B2") (pintype "bidirectional"))
    )
    (net (code "47") (name "/D14") (class "Default")
      (node (ref "R129") (pin "2") (pinfunction "2_2") (pintype "passive"))
      (node (ref "U101") (pin "B1") (pinfunction "DQ14_B1") (pintype "bidirectional"))
    )
    (net (code "48") (name "/D15") (class "Default")
      (node (ref "R130") (pin "2") (pinfunction "2_2") (pintype "passive"))
      (node (ref "U101") (pin "A2") (pinfunction "DQ15_A2") (pintype "bidirectional"))
    )
    (net (code "49") (name "/DD0") (class "Default")
      (node (ref "R101") (pin "1") (pinfunction "1_1") (pintype "passive"))
      (node (ref "U100") (pin "M9") (pinfunction "D0_M9") (pintype "bidirectional"))
    )
    (net (code "50") (name "/DD1") (class "Default")
      (node (ref "R103") (pin "1") (pinfunction "1_1") (pintype "passive"))
      (node (ref "U100") (pin "N9") (pinfunction "D1_N9") (pintype "bidirectional"))
    )
    (net (code "51") (name "/DD2") (class "Default")
      (node (ref "R105") (pin "1") (pinfunction "1_1") (pintype "passive"))
      (node (ref "U100") (pin "M8") (pinfunction "D2_M8") (pintype "bidirectional"))
    )
    (net (code "52") (name "/DD3") (class "Default")
      (node (ref "R107") (pin "1") (pinfunction "1_1") (pintype "passive"))
      (node (ref "U100") (pin "P11") (pinfunction "D3_P11") (pintype "bidirectional"))
    )
    (net (code "53") (name "/DD4") (class "Default")
      (node (ref "R109") (pin "1") (pinfunction "1_1") (pintype "passive"))
      (node (ref "U100") (pin "P10") (pinfunction "D4_P10") (pintype "bidirectional"))
    )
    (net (code "54") (name "/DD5") (class "Default")
      (node (ref "R111") (pin "1") (pinfunction "1_1") (pintype "passive"))
      (node (ref "U100") (pin "N8") (pinfunction "D5_N8") (pintype "bidirectional"))
    )
    (net (code "55") (name "/DD6") (class "Default")
      (node (ref "R113") (pin "1") (pinfunction "1_1") (pintype "passive"))
      (node (ref "U100") (pin "P9") (pinfunction "D6_P9") (pintype "bidirectional"))
    )
    (net (code "56") (name "/DD7") (class "Default")
      (node (ref "R115") (pin "1") (pinfunction "1_1") (pintype "passive"))
      (node (ref "U100") (pin "P8") (pinfunction "D7_P8") (pintype "bidirectional"))
    )
    (net (code "57") (name "/DD8") (class "Default")
      (node (ref "R117") (pin "1") (pinfunction "1_1") (pintype "passive"))
      (node (ref "U100") (pin "P7") (pinfunction "D8_P7") (pintype "bidirectional"))
    )
    (net (code "58") (name "/DD9") (class "Default")
      (node (ref "R119") (pin "1") (pinfunction "1_1") (pintype "passive"))
      (node (ref "U100") (pin "N7") (pinfunction "D9_N7") (pintype "bidirectional"))
    )
    (net (code "59") (name "/DD10") (class "Default")
      (node (ref "R121") (pin "1") (pinfunction "1_1") (pintype "passive"))
      (node (ref "U100") (pin "M7") (pinfunction "D10_M7") (pintype "bidirectional"))
    )
    (net (code "60") (name "/DD11") (class "Default")
      (node (ref "R123") (pin "1") (pinfunction "1_1") (pintype "passive"))
      (node (ref "U100") (pin "P6") (pinfunction "D11_P6") (pintype "bidirectional"))
    )
    (net (code "61") (name "/DD12") (class "Default")
      (node (ref "R125") (pin "1") (pinfunction "1_1") (pintype "passive"))
      (node (ref "U100") (pin "M6") (pinfunction "D12_M6") (pintype "bidirectional"))
    )
    (net (code "62") (name "/DD13") (class "Default")
      (node (ref "R127") (pin "1") (pinfunction "1_1") (pintype "passive"))
      (node (ref "U100") (pin "N6") (pinfunction "D13_N6") (pintype "bidirectional"))
    )
    (net (code "63") (name "/DD14") (class "Default")
      (node (ref "R129") (pin "1") (pinfunction "1_1") (pintype "passive"))
      (node (ref "U100") (pin "P5") (pinfunction "D14_P5") (pintype "bidirectional"))
    )
    (net (code "64") (name "/DD15") (class "Default")
      (node (ref "R130") (pin "1") (pinfunction "1_1") (pintype "passive"))
      (node (ref "U100") (pin "P4") (pinfunction "D15_P4") (pintype "bidirectional"))
    )
    (net (code "66") (name "/EXT_WAKE") (class "Default")
      (node (ref "U100") (pin "B14") (pinfunction "EXT_WAKE_B14") (pintype "output"))
    )
    (net (code "67") (name "/MCLK") (class "Default")
      (node (ref "U100") (pin "A11") (pinfunction "CLKBUF_A11") (pintype "output"))
    )
    (net (code "68") (name "/SCKE") (class "Default")
      (node (ref "R141") (pin "1") (pinfunction "1_1") (pintype "passive"))
      (node (ref "R144") (pin "2") (pinfunction "2_2") (pintype "passive"))
      (node (ref "U101") (pin "F3") (pinfunction "CKE_F3") (pintype "input"))
    )
    (net (code "69") (name "/~{RESET}") (class "Default")
      (node (ref "U100") (pin "B10") (pinfunction "~{RESET}_B10") (pintype "input"))
    )
    (net (code "70") (name "/~{SCAS}") (class "Default")
      (node (ref "R136") (pin "1") (pinfunction "1_1") (pintype "passive"))
      (node (ref "U101") (pin "F7") (pinfunction "~{CAS}_F7") (pintype "input"))
    )
    (net (code "71") (name "/~{SMS}") (class "Default")
      (node (ref "R140") (pin "1") (pinfunction "1_1") (pintype "passive"))
      (node (ref "U101") (pin "G9") (pinfunction "~{CS}_G9") (pintype "input"))
    )
    (net (code "72") (name "/~{SRAS}") (class "Default")
      (node (ref "R138") (pin "1") (pinfunction "1_1") (pintype "passive"))
      (node (ref "U101") (pin "F8") (pinfunction "~{RAS}_F8") (pintype "input"))
    )
    (net (code "73") (name "/~{SWE}") (class "Default")
      (node (ref "R134") (pin "1") (pinfunction "1_1") (pintype "passive"))
      (node (ref "U101") (pin "F9") (pinfunction "~{WE}_F9") (pintype "input"))
    )
    (net (code "74") (name "GND") (class "Default")
      (node (ref "C100") (pin "1") (pinfunction "1_1") (pintype "passive"))
      (node (ref "C101") (pin "1") (pinfunction "1_1") (pintype "passive"))
      (node (ref "C102") (pin "1") (pinfunction "1_1") (pintype "passive"))
      (node (ref "C103") (pin "1") (pinfunction "1_1") (pintype "passive"))
      (node (ref "C104") (pin "1") (pinfunction "1_1") (pintype "passive"))
      (node (ref "C105") (pin "1") (pinfunction "1_1") (pintype "passive"))
      (node (ref "C106") (pin "1") (pinfunction "1_1") (pintype "passive"))
      (node (ref "C107") (pin "1") (pinfunction "1_1") (pintype "passive"))
      (node (ref "C108") (pin "1") (pinfunction "1_1") (pintype "passive"))
      (node (ref "C109") (pin "1") (pinfunction "1_1") (pintype "passive"))
      (node (ref "C110") (pin "1") (pinfunction "1_1") (pintype "passive"))
      (node (ref "R143") (pin "1") (pinfunction "1_1") (pintype "passive"))
      (node (ref "R144") (pin "1") (pinfunction "1_1") (pintype "passive"))
      (node (ref "U101") (pin "A1") (pinfunction "VSS_A1") (pintype "power_in"))
      (node (ref "U101") (pin "A3") (pinfunction "VSSQ_A3") (pintype "power_in"))
      (node (ref "U101") (pin "B7") (pinfunction "VSSQ_B7") (pintype "power_in"))
      (node (ref "U101") (pin "C3") (pinfunction "VSSQ_C3") (pintype "power_in"))
      (node (ref "U101") (pin "D7") (pinfunction "VSSQ_D7") (pintype "power_in"))
      (node (ref "U101") (pin "E3") (pinfunction "VSS_E3") (pintype "power_in"))
      (node (ref "U101") (pin "J1") (pinfunction "VSS_J1") (pintype "power_in"))
      (node (ref "Y100") (pin "2") (pinfunction "GND_2") (pintype "passive"))
    )
    (net (code "75") (name "Net-(U100A-A11)") (class "Default")
      (node (ref "TP104") (pin "1") (pinfunction "1_1") (pintype "passive"))
      (node (ref "U100") (pin "N13") (pinfunction "A11_N13") (pintype "output"))
    )
    (net (code "76") (name "Net-(U100A-A14)") (class "Default")
      (node (ref "TP100") (pin "1") (pinfunction "1_1") (pintype "passive"))
      (node (ref "U100") (pin "N12") (pinfunction "A14_N12") (pintype "output"))
    )
    (net (code "77") (name "Net-(U100A-A15)") (class "Default")
      (node (ref "TP101") (pin "1") (pinfunction "1_1") (pintype "passive"))
      (node (ref "U100") (pin "J12") (pinfunction "A15_J12") (pintype "output"))
    )
    (net (code "78") (name "Net-(U100A-A16)") (class "Default")
      (node (ref "TP102") (pin "1") (pinfunction "1_1") (pintype "passive"))
      (node (ref "U100") (pin "N11") (pinfunction "A16_N11") (pintype "output"))
    )
    (net (code "79") (name "Net-(U100A-A17)") (class "Default")
      (node (ref "TP103") (pin "1") (pinfunction "1_1") (pintype "passive"))
      (node (ref "U100") (pin "M10") (pinfunction "A17_M10") (pintype "output"))
    )
    (net (code "80") (name "Net-(U100A-A18)") (class "Default")
      (node (ref "R126") (pin "2") (pinfunction "2_2") (pintype "passive"))
      (node (ref "U100") (pin "N10") (pinfunction "A18_N10") (pintype "output"))
    )
    (net (code "81") (name "Net-(U100A-A19)") (class "Default")
      (node (ref "R128") (pin "2") (pinfunction "2_2") (pintype "passive"))
      (node (ref "U100") (pin "P12") (pinfunction "A19_P12") (pintype "output"))
    )
    (net (code "82") (name "Net-(U100A-CLKIN)") (class "Default")
      (node (ref "R139") (pin "2") (pinfunction "2_2") (pintype "passive"))
      (node (ref "U100") (pin "A13") (pinfunction "CLKIN_A13") (pintype "input"))
    )
    (net (code "83") (name "Net-(U100A-CLKOUT)") (class "Default")
      (node (ref "R142") (pin "1") (pinfunction "1_1") (pintype "passive"))
      (node (ref "U100") (pin "D13") (pinfunction "CLKOUT_D13") (pintype "output"))
    )
    (net (code "84") (name "Net-(U100A-RTXI)") (class "Default")
      (node (ref "C109") (pin "2") (pinfunction "2_2") (pintype "passive"))
      (node (ref "R145") (pin "1") (pinfunction "1_1") (pintype "passive"))
      (node (ref "U100") (pin "C11") (pinfunction "RTXI_C11") (pintype "input"))
      (node (ref "X100") (pin "1") (pinfunction "OSC1_1") (pintype "passive"))
    )
    (net (code "85") (name "Net-(U100A-RTXO)") (class "Default")
      (node (ref "C110") (pin "2") (pinfunction "2_2") (pintype "passive"))
      (node (ref "R145") (pin "2") (pinfunction "2_2") (pintype "passive"))
      (node (ref "U100") (pin "C12") (pinfunction "RTXO_C12") (pintype "output"))
      (node (ref "X100") (pin "4") (pinfunction "OSC2_4") (pintype "passive"))
    )
    (net (code "86") (name "Net-(U100A-SCKE)") (class "Default")
      (node (ref "R141") (pin "2") (pinfunction "2_2") (pintype "passive"))
      (node (ref "U100") (pin "F13") (pinfunction "SCKE_F13") (pintype "output"))
    )
    (net (code "87") (name "Net-(U100A-XTAL)") (class "Default")
      (node (ref "TP107") (pin "1") (pinfunction "1_1") (pintype "passive"))
      (node (ref "U100") (pin "A12") (pinfunction "XTAL_A12") (pintype "output"))
    )
    (net (code "88") (name "Net-(U100A-~{ABE}0)") (class "Default")
      (node (ref "R132") (pin "1") (pinfunction "1_1") (pintype "passive"))
      (node (ref "U100") (pin "H13") (pinfunction "~{ABE}0_H13") (pintype "output"))
    )
    (net (code "89") (name "Net-(U100A-~{ABE}1)") (class "Default")
      (node (ref "R131") (pin "1") (pinfunction "1_1") (pintype "passive"))
      (node (ref "U100") (pin "J13") (pinfunction "~{ABE}1_J13") (pintype "output"))
    )
    (net (code "90") (name "Net-(U100A-~{AMS}0)") (class "Default")
      (node (ref "R135") (pin "1") (pinfunction "1_1") (pintype "passive"))
      (node (ref "U100") (pin "D14") (pinfunction "~{AMS}0_D14") (pintype "output"))
    )
    (net (code "91") (name "Net-(U100A-~{AMS}1)") (class "Default")
      (node (ref "R133") (pin "1") (pinfunction "1_1") (pintype "passive"))
      (node (ref "U100") (pin "F14") (pinfunction "~{AMS}1_F14") (pintype "output"))
    )
    (net (code "92") (name "Net-(U100A-~{ARE})") (class "Default")
      (node (ref "TP105") (pin "1") (pinfunction "1_1") (pintype "passive"))
      (node (ref "U100") (pin "E13") (pinfunction "~{ARE}_E13") (pintype "output"))
    )
    (net (code "93") (name "Net-(U100A-~{AWE})") (class "Default")
      (node (ref "TP106") (pin "1") (pinfunction "1_1") (pintype "passive"))
      (node (ref "U100") (pin "E14") (pinfunction "~{AWE}_E14") (pintype "output"))
    )
    (net (code "94") (name "Net-(U100A-~{NMI})") (class "Default")
      (node (ref "R146") (pin "2") (pinfunction "2_2") (pintype "passive"))
      (node (ref "U100") (pin "B11") (pinfunction "~{NMI}_B11") (pintype "input"))
    )
    (net (code "95") (name "Net-(U100A-~{PG})") (class "Default")
      (node (ref "C101") (pin "2") (pinfunction "2_2") (pintype "passive"))
      (node (ref "R137") (pin "1") (pinfunction "1_1") (pintype "passive"))
      (node (ref "R143") (pin "2") (pinfunction "2_2") (pintype "passive"))
      (node (ref "U100") (pin "C13") (pinfunction "~{PG}_C13") (pintype "input"))
    )
    (net (code "96") (name "Net-(U100A-~{SCAS})") (class "Default")
      (node (ref "R136") (pin "2") (pinfunction "2_2") (pintype "passive"))
      (node (ref "U100") (pin "H14") (pinfunction "~{SCAS}_H14") (pintype "output"))
    )
    (net (code "97") (name "Net-(U100A-~{SMS})") (class "Default")
      (node (ref "R140") (pin "2") (pinfunction "2_2") (pintype "passive"))
      (node (ref "U100") (pin "F12") (pinfunction "~{SMS}_F12") (pintype "output"))
    )
    (net (code "98") (name "Net-(U100A-~{SRAS})") (class "Default")
      (node (ref "R138") (pin "2") (pinfunction "2_2") (pintype "passive"))
      (node (ref "U100") (pin "G13") (pinfunction "~{SRAS}_G13") (pintype "output"))
    )
    (net (code "99") (name "Net-(U100A-~{SWE})") (class "Default")
      (node (ref "R134") (pin "2") (pinfunction "2_2") (pintype "passive"))
      (node (ref "U100") (pin "G12") (pinfunction "~{SWE}_G12") (pintype "output"))
    )
    (net (code "100") (name "Net-(Y100-OUTPUT)") (class "Default")
      (node (ref "R139") (pin "1") (pinfunction "1_1") (pintype "passive"))
      (node (ref "Y100") (pin "3") (pinfunction "OUTPUT_3") (pintype "passive"))
    )
    (net (code "101") (name "VCC3V3") (class "Default")
      (node (ref "C100") (pin "2") (pinfunction "2_2") (pintype "passive"))
      (node (ref "C102") (pin "2") (pinfunction "2_2") (pintype "passive"))
      (node (ref "C103") (pin "2") (pinfunction "2_2") (pintype "passive"))
      (node (ref "C104") (pin "2") (pinfunction "2_2") (pintype "passive"))
      (node (ref "C105") (pin "2") (pinfunction "2_2") (pintype "passive"))
      (node (ref "C106") (pin "2") (pinfunction "2_2") (pintype "passive"))
      (node (ref "C107") (pin "2") (pinfunction "2_2") (pintype "passive"))
      (node (ref "C108") (pin "2") (pinfunction "2_2") (pintype "passive"))
      (node (ref "R133") (pin "2") (pinfunction "2_2") (pintype "passive"))
      (node (ref "R135") (pin "2") (pinfunction "2_2") (pintype "passive"))
      (node (ref "R137") (pin "2") (pinfunction "2_2") (pintype "passive"))
      (node (ref "R146") (pin "1") (pinfunction "1_1") (pintype "passive"))
      (node (ref "U101") (pin "A7") (pinfunction "VDDQ_A7") (pintype "power_in"))
      (node (ref "U101") (pin "A9") (pinfunction "VDD_A9") (pintype "power_in"))
      (node (ref "U101") (pin "B3") (pinfunction "VDDQ_B3") (pintype "power_in"))
      (node (ref "U101") (pin "C7") (pinfunction "VDDQ_C7") (pintype "power_in"))
      (node (ref "U101") (pin "D3") (pinfunction "VDDQ_D3") (pintype "power_in"))
      (node (ref "U101") (pin "E7") (pinfunction "VDD_E7") (pintype "power_in"))
      (node (ref "U101") (pin "J9") (pinfunction "VDD_J9") (pintype "power_in"))
      (node (ref "Y100") (pin "4") (pinfunction "VCC_4") (pintype "passive"))
    )
    (net (code "102") (name "unconnected-(U100A-NC-PadC14)") (class "Default")
      (node (ref "U100") (pin "C14") (pinfunction "NC_C14") (pintype "passive+no_connect"))
    )
    (net (code "103") (name "unconnected-(U101-NC-PadE2)") (class "Default")
      (node (ref "U101") (pin "E2") (pinfunction "NC_E2") (pintype "passive+no_connect"))
    )
    (net (code "104") (name "unconnected-(Y100-EN{slash}~{DIS}-Pad1)") (class "Default")
      (node (ref "Y100") (pin "1") (pinfunction "EN/~{DIS}_1") (pintype "passive+no_connect"))
    )
  )
)
